# btmodbreakout.net
KiCad netlist of a schematic drawn in EAGLE
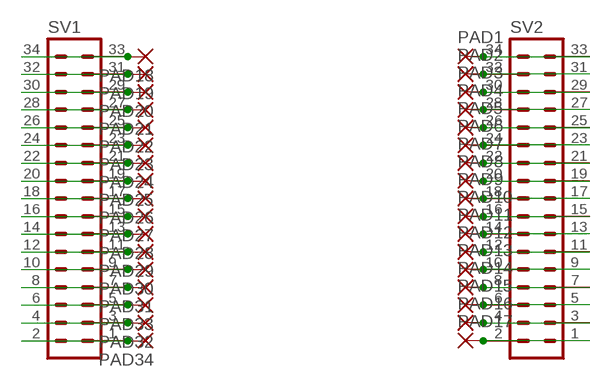
[diagram p0: schematic, sheet 1]

(export (version "E")
  (design (tool "Eeschema 10.0.6"))
  (components
    (comp (ref "PAD1")
      (value "SMD2")
      (footprint "eagle-import:SMD1,27-2,54")
      (libsource (lib "eagle-import") (part "SMD2"))
    )
    (comp (ref "PAD2")
      (value "SMD2")
      (footprint "eagle-import:SMD1,27-2,54")
      (libsource (lib "eagle-import") (part "SMD2"))
    )
    (comp (ref "PAD3")
      (value "SMD2")
      (footprint "eagle-import:SMD1,27-2,54")
      (libsource (lib "eagle-import") (part "SMD2"))
    )
    (comp (ref "PAD4")
      (value "SMD2")
      (footprint "eagle-import:SMD1,27-2,54")
      (libsource (lib "eagle-import") (part "SMD2"))
    )
    (comp (ref "PAD5")
      (value "SMD2")
      (footprint "eagle-import:SMD1,27-2,54")
      (libsource (lib "eagle-import") (part "SMD2"))
    )
    (comp (ref "PAD6")
      (value "SMD2")
      (footprint "eagle-import:SMD1,27-2,54")
      (libsource (lib "eagle-import") (part "SMD2"))
    )
    (comp (ref "PAD7")
      (value "SMD2")
      (footprint "eagle-import:SMD1,27-2,54")
      (libsource (lib "eagle-import") (part "SMD2"))
    )
    (comp (ref "PAD8")
      (value "SMD2")
      (footprint "eagle-import:SMD1,27-2,54")
      (libsource (lib "eagle-import") (part "SMD2"))
    )
    (comp (ref "PAD9")
      (value "SMD2")
      (footprint "eagle-import:SMD1,27-2,54")
      (libsource (lib "eagle-import") (part "SMD2"))
    )
    (comp (ref "PAD10")
      (value "SMD2")
      (footprint "eagle-import:SMD1,27-2,54")
      (libsource (lib "eagle-import") (part "SMD2"))
    )
    (comp (ref "PAD11")
      (value "SMD2")
      (footprint "eagle-import:SMD1,27-2,54")
      (libsource (lib "eagle-import") (part "SMD2"))
    )
    (comp (ref "PAD12")
      (value "SMD2")
      (footprint "eagle-import:SMD1,27-2,54")
      (libsource (lib "eagle-import") (part "SMD2"))
    )
    (comp (ref "PAD13")
      (value "SMD2")
      (footprint "eagle-import:SMD1,27-2,54")
      (libsource (lib "eagle-import") (part "SMD2"))
    )
    (comp (ref "PAD14")
      (value "SMD2")
      (footprint "eagle-import:SMD1,27-2,54")
      (libsource (lib "eagle-import") (part "SMD2"))
    )
    (comp (ref "PAD15")
      (value "SMD2")
      (footprint "eagle-import:SMD1,27-2,54")
      (libsource (lib "eagle-import") (part "SMD2"))
    )
    (comp (ref "PAD16")
      (value "SMD2")
      (footprint "eagle-import:SMD1,27-2,54")
      (libsource (lib "eagle-import") (part "SMD2"))
    )
    (comp (ref "PAD17")
      (value "SMD2")
      (footprint "eagle-import:SMD1,27-2,54")
      (libsource (lib "eagle-import") (part "SMD2"))
    )
    (comp (ref "PAD18")
      (value "SMD2")
      (footprint "eagle-import:SMD1,27-2,54")
      (libsource (lib "eagle-import") (part "SMD2"))
    )
    (comp (ref "PAD19")
      (value "SMD2")
      (footprint "eagle-import:SMD1,27-2,54")
      (libsource (lib "eagle-import") (part "SMD2"))
    )
    (comp (ref "PAD20")
      (value "SMD2")
      (footprint "eagle-import:SMD1,27-2,54")
      (libsource (lib "eagle-import") (part "SMD2"))
    )
    (comp (ref "PAD21")
      (value "SMD2")
      (footprint "eagle-import:SMD1,27-2,54")
      (libsource (lib "eagle-import") (part "SMD2"))
    )
    (comp (ref "PAD22")
      (value "SMD2")
      (footprint "eagle-import:SMD1,27-2,54")
      (libsource (lib "eagle-import") (part "SMD2"))
    )
    (comp (ref "PAD23")
      (value "SMD2")
      (footprint "eagle-import:SMD1,27-2,54")
      (libsource (lib "eagle-import") (part "SMD2"))
    )
    (comp (ref "PAD24")
      (value "SMD2")
      (footprint "eagle-import:SMD1,27-2,54")
      (libsource (lib "eagle-import") (part "SMD2"))
    )
    (comp (ref "PAD25")
      (value "SMD2")
      (footprint "eagle-import:SMD1,27-2,54")
      (libsource (lib "eagle-import") (part "SMD2"))
    )
    (comp (ref "PAD26")
      (value "SMD2")
      (footprint "eagle-import:SMD1,27-2,54")
      (libsource (lib "eagle-import") (part "SMD2"))
    )
    (comp (ref "PAD27")
      (value "SMD2")
      (footprint "eagle-import:SMD1,27-2,54")
      (libsource (lib "eagle-import") (part "SMD2"))
    )
    (comp (ref "PAD28")
      (value "SMD2")
      (footprint "eagle-import:SMD1,27-2,54")
      (libsource (lib "eagle-import") (part "SMD2"))
    )
    (comp (ref "PAD29")
      (value "SMD2")
      (footprint "eagle-import:SMD1,27-2,54")
      (libsource (lib "eagle-import") (part "SMD2"))
    )
    (comp (ref "PAD30")
      (value "SMD2")
      (footprint "eagle-import:SMD1,27-2,54")
      (libsource (lib "eagle-import") (part "SMD2"))
    )
    (comp (ref "PAD31")
      (value "SMD2")
      (footprint "eagle-import:SMD1,27-2,54")
      (libsource (lib "eagle-import") (part "SMD2"))
    )
    (comp (ref "PAD32")
      (value "SMD2")
      (footprint "eagle-import:SMD1,27-2,54")
      (libsource (lib "eagle-import") (part "SMD2"))
    )
    (comp (ref "PAD33")
      (value "SMD2")
      (footprint "eagle-import:SMD1,27-2,54")
      (libsource (lib "eagle-import") (part "SMD2"))
    )
    (comp (ref "PAD34")
      (value "SMD2")
      (footprint "eagle-import:SMD1,27-2,54")
      (libsource (lib "eagle-import") (part "SMD2"))
    )
    (comp (ref "SV1")
      (value "MA17-2")
      (footprint "eagle-import:MA17-2")
      (libsource (lib "eagle-import") (part "MA17-2"))
    )
    (comp (ref "SV2")
      (value "MA17-2")
      (footprint "eagle-import:MA17-2")
      (libsource (lib "eagle-import") (part "MA17-2"))
    )
  )
  (nets
    (net (code "1") (name "Net-(PAD1-P)") (class "Default")
      (node (ref "PAD1") (pin "1") (pinfunction "P_1") (pintype "passive"))
      (node (ref "SV2") (pin "33") (pinfunction "33_33") (pintype "passive"))
      (node (ref "SV2") (pin "34") (pinfunction "34_34") (pintype "passive"))
    )
    (net (code "2") (name "Net-(PAD2-P)") (class "Default")
      (node (ref "PAD2") (pin "1") (pinfunction "P_1") (pintype "passive"))
      (node (ref "SV2") (pin "31") (pinfunction "31_31") (pintype "passive"))
      (node (ref "SV2") (pin "32") (pinfunction "32_32") (pintype "passive"))
    )
    (net (code "3") (name "Net-(PAD3-P)") (class "Default")
      (node (ref "PAD3") (pin "1") (pinfunction "P_1") (pintype "passive"))
      (node (ref "SV2") (pin "29") (pinfunction "29_29") (pintype "passive"))
      (node (ref "SV2") (pin "30") (pinfunction "30_30") (pintype "passive"))
    )
    (net (code "4") (name "Net-(PAD4-P)") (class "Default")
      (node (ref "PAD4") (pin "1") (pinfunction "P_1") (pintype "passive"))
      (node (ref "SV2") (pin "27") (pinfunction "27_27") (pintype "passive"))
      (node (ref "SV2") (pin "28") (pinfunction "28_28") (pintype "passive"))
    )
    (net (code "5") (name "Net-(PAD5-P)") (class "Default")
      (node (ref "PAD5") (pin "1") (pinfunction "P_1") (pintype "passive"))
      (node (ref "SV2") (pin "25") (pinfunction "25_25") (pintype "passive"))
      (node (ref "SV2") (pin "26") (pinfunction "26_26") (pintype "passive"))
    )
    (net (code "6") (name "Net-(PAD6-P)") (class "Default")
      (node (ref "PAD6") (pin "1") (pinfunction "P_1") (pintype "passive"))
      (node (ref "SV2") (pin "23") (pinfunction "23_23") (pintype "passive"))
      (node (ref "SV2") (pin "24") (pinfunction "24_24") (pintype "passive"))
    )
    (net (code "7") (name "Net-(PAD7-P)") (class "Default")
      (node (ref "PAD7") (pin "1") (pinfunction "P_1") (pintype "passive"))
      (node (ref "SV2") (pin "21") (pinfunction "21_21") (pintype "passive"))
      (node (ref "SV2") (pin "22") (pinfunction "22_22") (pintype "passive"))
    )
    (net (code "8") (name "Net-(PAD8-P)") (class "Default")
      (node (ref "PAD8") (pin "1") (pinfunction "P_1") (pintype "passive"))
      (node (ref "SV2") (pin "19") (pinfunction "19_19") (pintype "passive"))
      (node (ref "SV2") (pin "20") (pinfunction "20_20") (pintype "passive"))
    )
    (net (code "9") (name "Net-(PAD9-P)") (class "Default")
      (node (ref "PAD9") (pin "1") (pinfunction "P_1") (pintype "passive"))
      (node (ref "SV2") (pin "17") (pinfunction "17_17") (pintype "passive"))
      (node (ref "SV2") (pin "18") (pinfunction "18_18") (pintype "passive"))
    )
    (net (code "10") (name "Net-(PAD10-P)") (class "Default")
      (node (ref "PAD10") (pin "1") (pinfunction "P_1") (pintype "passive"))
      (node (ref "SV2") (pin "15") (pinfunction "15_15") (pintype "passive"))
      (node (ref "SV2") (pin "16") (pinfunction "16_16") (pintype "passive"))
    )
    (net (code "11") (name "Net-(PAD11-P)") (class "Default")
      (node (ref "PAD11") (pin "1") (pinfunction "P_1") (pintype "passive"))
      (node (ref "SV2") (pin "13") (pinfunction "13_13") (pintype "passive"))
      (node (ref "SV2") (pin "14") (pinfunction "14_14") (pintype "passive"))
    )
    (net (code "12") (name "Net-(PAD12-P)") (class "Default")
      (node (ref "PAD12") (pin "1") (pinfunction "P_1") (pintype "passive"))
      (node (ref "SV2") (pin "11") (pinfunction "11_11") (pintype "passive"))
      (node (ref "SV2") (pin "12") (pinfunction "12_12") (pintype "passive"))
    )
    (net (code "13") (name "Net-(PAD13-P)") (class "Default")
      (node (ref "PAD13") (pin "1") (pinfunction "P_1") (pintype "passive"))
      (node (ref "SV2") (pin "10") (pinfunction "10_10") (pintype "passive"))
      (node (ref "SV2") (pin "9") (pinfunction "9_9") (pintype "passive"))
    )
    (net (code "14") (name "Net-(PAD14-P)") (class "Default")
      (node (ref "PAD14") (pin "1") (pinfunction "P_1") (pintype "passive"))
      (node (ref "SV2") (pin "7") (pinfunction "7_7") (pintype "passive"))
      (node (ref "SV2") (pin "8") (pinfunction "8_8") (pintype "passive"))
    )
    (net (code "15") (name "Net-(PAD15-P)") (class "Default")
      (node (ref "PAD15") (pin "1") (pinfunction "P_1") (pintype "passive"))
      (node (ref "SV2") (pin "5") (pinfunction "5_5") (pintype "passive"))
      (node (ref "SV2") (pin "6") (pinfunction "6_6") (pintype "passive"))
    )
    (net (code "16") (name "Net-(PAD16-P)") (class "Default")
      (node (ref "PAD16") (pin "1") (pinfunction "P_1") (pintype "passive"))
      (node (ref "SV2") (pin "3") (pinfunction "3_3") (pintype "passive"))
      (node (ref "SV2") (pin "4") (pinfunction "4_4") (pintype "passive"))
    )
    (net (code "17") (name "Net-(PAD17-P)") (class "Default")
      (node (ref "PAD17") (pin "1") (pinfunction "P_1") (pintype "passive"))
      (node (ref "SV2") (pin "1") (pinfunction "1_1") (pintype "passive"))
      (node (ref "SV2") (pin "2") (pinfunction "2_2") (pintype "passive"))
    )
    (net (code "18") (name "Net-(PAD18-P)") (class "Default")
      (node (ref "PAD18") (pin "1") (pinfunction "P_1") (pintype "passive"))
      (node (ref "SV1") (pin "33") (pinfunction "33_33") (pintype "passive"))
      (node (ref "SV1") (pin "34") (pinfunction "34_34") (pintype "passive"))
    )
    (net (code "19") (name "Net-(PAD19-P)") (class "Default")
      (node (ref "PAD19") (pin "1") (pinfunction "P_1") (pintype "passive"))
      (node (ref "SV1") (pin "31") (pinfunction "31_31") (pintype "passive"))
      (node (ref "SV1") (pin "32") (pinfunction "32_32") (pintype "passive"))
    )
    (net (code "20") (name "Net-(PAD20-P)") (class "Default")
      (node (ref "PAD20") (pin "1") (pinfunction "P_1") (pintype "passive"))
      (node (ref "SV1") (pin "29") (pinfunction "29_29") (pintype "passive"))
      (node (ref "SV1") (pin "30") (pinfunction "30_30") (pintype "passive"))
    )
    (net (code "21") (name "Net-(PAD21-P)") (class "Default")
      (node (ref "PAD21") (pin "1") (pinfunction "P_1") (pintype "passive"))
      (node (ref "SV1") (pin "27") (pinfunction "27_27") (pintype "passive"))
      (node (ref "SV1") (pin "28") (pinfunction "28_28") (pintype "passive"))
    )
    (net (code "22") (name "Net-(PAD22-P)") (class "Default")
      (node (ref "PAD22") (pin "1") (pinfunction "P_1") (pintype "passive"))
      (node (ref "SV1") (pin "25") (pinfunction "25_25") (pintype "passive"))
      (node (ref "SV1") (pin "26") (pinfunction "26_26") (pintype "passive"))
    )
    (net (code "23") (name "Net-(PAD23-P)") (class "Default")
      (node (ref "PAD23") (pin "1") (pinfunction "P_1") (pintype "passive"))
      (node (ref "SV1") (pin "23") (pinfunction "23_23") (pintype "passive"))
      (node (ref "SV1") (pin "24") (pinfunction "24_24") (pintype "passive"))
    )
    (net (code "24") (name "Net-(PAD24-P)") (class "Default")
      (node (ref "PAD24") (pin "1") (pinfunction "P_1") (pintype "passive"))
      (node (ref "SV1") (pin "21") (pinfunction "21_21") (pintype "passive"))
      (node (ref "SV1") (pin "22") (pinfunction "22_22") (pintype "passive"))
    )
    (net (code "25") (name "Net-(PAD25-P)") (class "Default")
      (node (ref "PAD25") (pin "1") (pinfunction "P_1") (pintype "passive"))
      (node (ref "SV1") (pin "19") (pinfunction "19_19") (pintype "passive"))
      (node (ref "SV1") (pin "20") (pinfunction "20_20") (pintype "passive"))
    )
    (net (code "26") (name "Net-(PAD26-P)") (class "Default")
      (node (ref "PAD26") (pin "1") (pinfunction "P_1") (pintype "passive"))
      (node (ref "SV1") (pin "17") (pinfunction "17_17") (pintype "passive"))
      (node (ref "SV1") (pin "18") (pinfunction "18_18") (pintype "passive"))
    )
    (net (code "27") (name "Net-(PAD27-P)") (class "Default")
      (node (ref "PAD27") (pin "1") (pinfunction "P_1") (pintype "passive"))
      (node (ref "SV1") (pin "15") (pinfunction "15_15") (pintype "passive"))
      (node (ref "SV1") (pin "16") (pinfunction "16_16") (pintype "passive"))
    )
    (net (code "28") (name "Net-(PAD28-P)") (class "Default")
      (node (ref "PAD28") (pin "1") (pinfunction "P_1") (pintype "passive"))
      (node (ref "SV1") (pin "13") (pinfunction "13_13") (pintype "passive"))
      (node (ref "SV1") (pin "14") (pinfunction "14_14") (pintype "passive"))
    )
    (net (code "29") (name "Net-(PAD29-P)") (class "Default")
      (node (ref "PAD29") (pin "1") (pinfunction "P_1") (pintype "passive"))
      (node (ref "SV1") (pin "11") (pinfunction "11_11") (pintype "passive"))
      (node (ref "SV1") (pin "12") (pinfunction "12_12") (pintype "passive"))
    )
    (net (code "30") (name "Net-(PAD30-P)") (class "Default")
      (node (ref "PAD30") (pin "1") (pinfunction "P_1") (pintype "passive"))
      (node (ref "SV1") (pin "10") (pinfunction "10_10") (pintype "passive"))
      (node (ref "SV1") (pin "9") (pinfunction "9_9") (pintype "passive"))
    )
    (net (code "31") (name "Net-(PAD31-P)") (class "Default")
      (node (ref "PAD31") (pin "1") (pinfunction "P_1") (pintype "passive"))
      (node (ref "SV1") (pin "7") (pinfunction "7_7") (pintype "passive"))
      (node (ref "SV1") (pin "8") (pinfunction "8_8") (pintype "passive"))
    )
    (net (code "32") (name "Net-(PAD32-P)") (class "Default")
      (node (ref "PAD32") (pin "1") (pinfunction "P_1") (pintype "passive"))
      (node (ref "SV1") (pin "3") (pinfunction "3_3") (pintype "passive"))
      (node (ref "SV1") (pin "4") (pinfunction "4_4") (pintype "passive"))
    )
    (net (code "33") (name "Net-(PAD33-P)") (class "Default")
      (node (ref "PAD33") (pin "1") (pinfunction "P_1") (pintype "passive"))
      (node (ref "SV1") (pin "5") (pinfunction "5_5") (pintype "passive"))
      (node (ref "SV1") (pin "6") (pinfunction "6_6") (pintype "passive"))
    )
    (net (code "34") (name "Net-(PAD34-P)") (class "Default")
      (node (ref "PAD34") (pin "1") (pinfunction "P_1") (pintype "passive"))
      (node (ref "SV1") (pin "1") (pinfunction "1_1") (pintype "passive"))
      (node (ref "SV1") (pin "2") (pinfunction "2_2") (pintype "passive"))
    )
  )
)
